# RS422_TX.net
KiCad netlist of a schematic drawn in Altium Designer
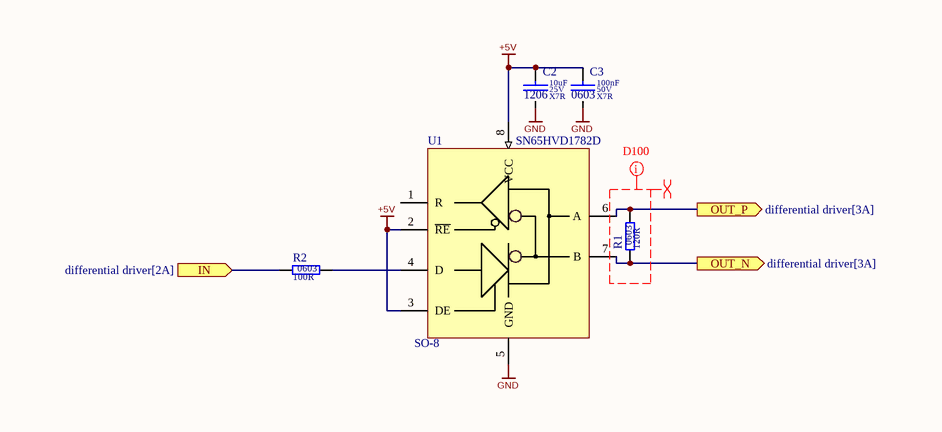
[diagram p0: RS422_TX.SchDoc]

(export (version "E")
  (design (tool "Eeschema 10.0.6"))
  (components
    (comp (ref "C2")
      (value "10uF")
      (footprint "C_1206_3216")
      (description "Capacitor")
      (fields
        (field (name "DIELECTRIC") "X7R")
        (field (name "VOLTAGE") "25V")
        (field (name "SCH_FOOTPRINT") "1206")
        (field (name "PART NUMBER") "C_10uF_25V_X7R_1206_10")
        (field (name "MANUFACTURER") "Samsung")
      )
      (libsource (lib "Library") (part "C"))
    )
    (comp (ref "C3")
      (value "100nF")
      (footprint "C_0603_1608")
      (description "Capacitor")
      (fields
        (field (name "DIELECTRIC") "X7R")
        (field (name "VOLTAGE") "50V")
        (field (name "SCH_FOOTPRINT") "0603")
        (field (name "PART NUMBER") "C_100nF_50V_X7R_0603_5")
        (field (name "MANUFACTURER") "Samsung")
      )
      (libsource (lib "Library") (part "C"))
    )
    (comp (ref "R1")
      (value "120R")
      (footprint "R_0603_1608")
      (fields
        (field (name "SCH_FOOTPRINT") "0603")
        (field (name "PART NUMBER") "R_120R_0603_1_AECQ0")
        (field (name "VOLTAGE") "75V")
        (field (name "POWER") "100mW")
      )
      (libsource (lib "Library") (part "R"))
    )
    (comp (ref "R2")
      (value "100R")
      (footprint "R_0603_1608")
      (fields
        (field (name "SCH_FOOTPRINT") "0603")
        (field (name "PART NUMBER") "R_100R_0603_1")
        (field (name "VOLTAGE") "50V")
        (field (name "POWER") "100mW")
      )
      (libsource (lib "Library") (part "R"))
    )
    (comp (ref "U1")
      (value "SN65HVD1782D")
      (footprint "SOP8_SO8_SOIC8_4X5X18")
      (description "Fault-Protected  RS-485  Transceivers  With 3.3-V to 5-V Operation")
      (fields
        (field (name "SCH_FOOTPRINT") "SO-8")
        (field (name "PART NUMBER") "U_SN65HVD1782DR")
        (field (name "MANUFACTURER") "Texas Instruments")
      )
      (libsource (lib "Library") (part "U_RS485_HD_GENERIC"))
    )
  )
  (nets
    (net (code "1") (name "+5V") (class "Default")
      (node (ref "C2") (pin "1") (pinfunction "1_1") (pintype "passive"))
      (node (ref "C3") (pin "1") (pinfunction "1_1") (pintype "passive"))
      (node (ref "U1") (pin "2") (pinfunction "~{RE}_2") (pintype "passive"))
      (node (ref "U1") (pin "3") (pinfunction "DE_3") (pintype "passive"))
      (node (ref "U1") (pin "8") (pinfunction "VCC_8") (pintype "input"))
    )
    (net (code "2") (name "/IN") (class "Default")
      (node (ref "R2") (pin "1") (pinfunction "1_1") (pintype "passive"))
    )
    (net (code "3") (name "/OUT_N") (class "Default")
      (node (ref "R1") (pin "1") (pinfunction "1_1") (pintype "passive"))
      (node (ref "U1") (pin "7") (pinfunction "B_7") (pintype "passive"))
    )
    (net (code "4") (name "/OUT_P") (class "Default")
      (node (ref "R1") (pin "2") (pinfunction "2_2") (pintype "passive"))
      (node (ref "U1") (pin "6") (pinfunction "A_6") (pintype "passive"))
    )
    (net (code "5") (name "GND") (class "Default")
      (node (ref "C2") (pin "2") (pinfunction "2_2") (pintype "passive"))
      (node (ref "C3") (pin "2") (pinfunction "2_2") (pintype "passive"))
      (node (ref "U1") (pin "5") (pinfunction "GND_5") (pintype "power_in"))
    )
    (net (code "6") (name "Net-(U1-D)") (class "Default")
      (node (ref "R2") (pin "2") (pinfunction "2_2") (pintype "passive"))
      (node (ref "U1") (pin "4") (pinfunction "D_4") (pintype "passive"))
    )
    (net (code "7") (name "unconnected-(U1-R-Pad1)") (class "Default")
      (node (ref "U1") (pin "1") (pinfunction "R_1") (pintype "passive"))
    )
  )
)
